# 2S_BATTERY_BALANCER_SCH.net
KiCad netlist of a schematic drawn in Altium Designer
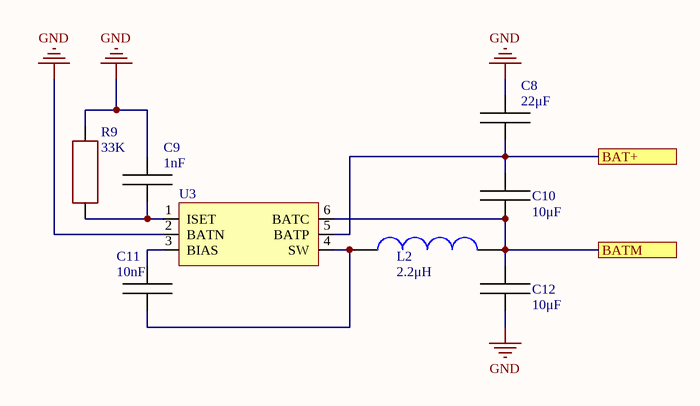
[diagram p0: 2S_BATTERY_BALANCER_SCH.SchDoc]

(export (version "E")
  (design (tool "Eeschema 10.0.6"))
  (components
    (comp (ref "C8")
      (value "22μF")
      (footprint "CAP: 1206")
      (fields (field (name "VOLTAGE") "??V") (field (name "Comment") "Cap_1206"))
      (libsource (lib "capacitor") (part "Cap_1206"))
    )
    (comp (ref "C9")
      (value "1nF")
      (footprint "CAP: 0402")
      (fields (field (name "VOLTAGE") "??V") (field (name "Comment") "Cap_0402"))
      (libsource (lib "capacitor") (part "Cap_0402"))
    )
    (comp (ref "C10")
      (value "10μF")
      (footprint "CAP: 0603")
      (fields (field (name "VOLTAGE") "??V") (field (name "Comment") "Cap_0603"))
      (libsource (lib "capacitor") (part "Cap_0603"))
    )
    (comp (ref "C11")
      (value "10nF")
      (footprint "CAP: 0402")
      (fields (field (name "VOLTAGE") "??V") (field (name "Comment") "Cap_0402"))
      (libsource (lib "capacitor") (part "Cap_0402"))
    )
    (comp (ref "C12")
      (value "10μF")
      (footprint "CAP: 0603")
      (fields (field (name "VOLTAGE") "??V") (field (name "Comment") "Cap_0603"))
      (libsource (lib "capacitor") (part "Cap_0603"))
    )
    (comp (ref "L2")
      (value "2.2μH")
      (footprint "CD43")
      (description "SMD Power Inductor")
      (fields (field (name "MANUFACTURER") "SUMIDA") (field (name "Comment") "CD43"))
      (libsource (lib "MY_INT_LIB") (part "CD43"))
    )
    (comp (ref "R9")
      (value "33K")
      (footprint "standard-case:RES: 0402")
      (fields (field (name "TOLERANCE") "±5%"))
      (libsource (lib "resistor") (part "Resistor_0402"))
    )
    (comp (ref "U3")
      (value "ETA3000")
      (footprint "SOT-23-6")
      (description "Inductive cell balancer")
      (fields (field (name "MANUFACTURER") "ETA"))
      (libsource (lib "MY_INT_LIB") (part "ETA3000"))
    )
  )
  (nets
    (net (code "1") (name "/BAT+") (class "Default")
      (node (ref "C10") (pin "1") (pinfunction "1_1") (pintype "passive"))
      (node (ref "C8") (pin "1") (pinfunction "1_1") (pintype "passive"))
      (node (ref "U3") (pin "5") (pinfunction "BATP_5") (pintype "passive"))
    )
    (net (code "2") (name "/BATM") (class "Default")
      (node (ref "C10") (pin "2") (pinfunction "2_2") (pintype "passive"))
      (node (ref "C12") (pin "1") (pinfunction "1_1") (pintype "passive"))
      (node (ref "L2") (pin "1") (pinfunction "1_1") (pintype "passive"))
      (node (ref "U3") (pin "6") (pinfunction "BATC_6") (pintype "passive"))
    )
    (net (code "3") (name "GND") (class "Default")
      (node (ref "C12") (pin "2") (pinfunction "2_2") (pintype "passive"))
      (node (ref "C8") (pin "2") (pinfunction "2_2") (pintype "passive"))
      (node (ref "C9") (pin "2") (pinfunction "2_2") (pintype "passive"))
      (node (ref "R9") (pin "2") (pinfunction "2_2") (pintype "passive"))
      (node (ref "U3") (pin "2") (pinfunction "BATN_2") (pintype "passive"))
    )
    (net (code "4") (name "Net-(U3-BIAS)") (class "Default")
      (node (ref "C11") (pin "2") (pinfunction "2_2") (pintype "passive"))
      (node (ref "U3") (pin "3") (pinfunction "BIAS_3") (pintype "passive"))
    )
    (net (code "5") (name "Net-(U3-ISET)") (class "Default")
      (node (ref "C9") (pin "1") (pinfunction "1_1") (pintype "passive"))
      (node (ref "R9") (pin "1") (pinfunction "1_1") (pintype "passive"))
      (node (ref "U3") (pin "1") (pinfunction "ISET_1") (pintype "passive"))
    )
    (net (code "6") (name "Net-(U3-SW)") (class "Default")
      (node (ref "C11") (pin "1") (pinfunction "1_1") (pintype "passive"))
      (node (ref "L2") (pin "2") (pinfunction "2_2") (pintype "passive"))
      (node (ref "U3") (pin "4") (pinfunction "SW_4") (pintype "passive"))
    )
  )
)
